# barnabas_noggin_V4.net
KiCad netlist of a schematic drawn in EAGLE
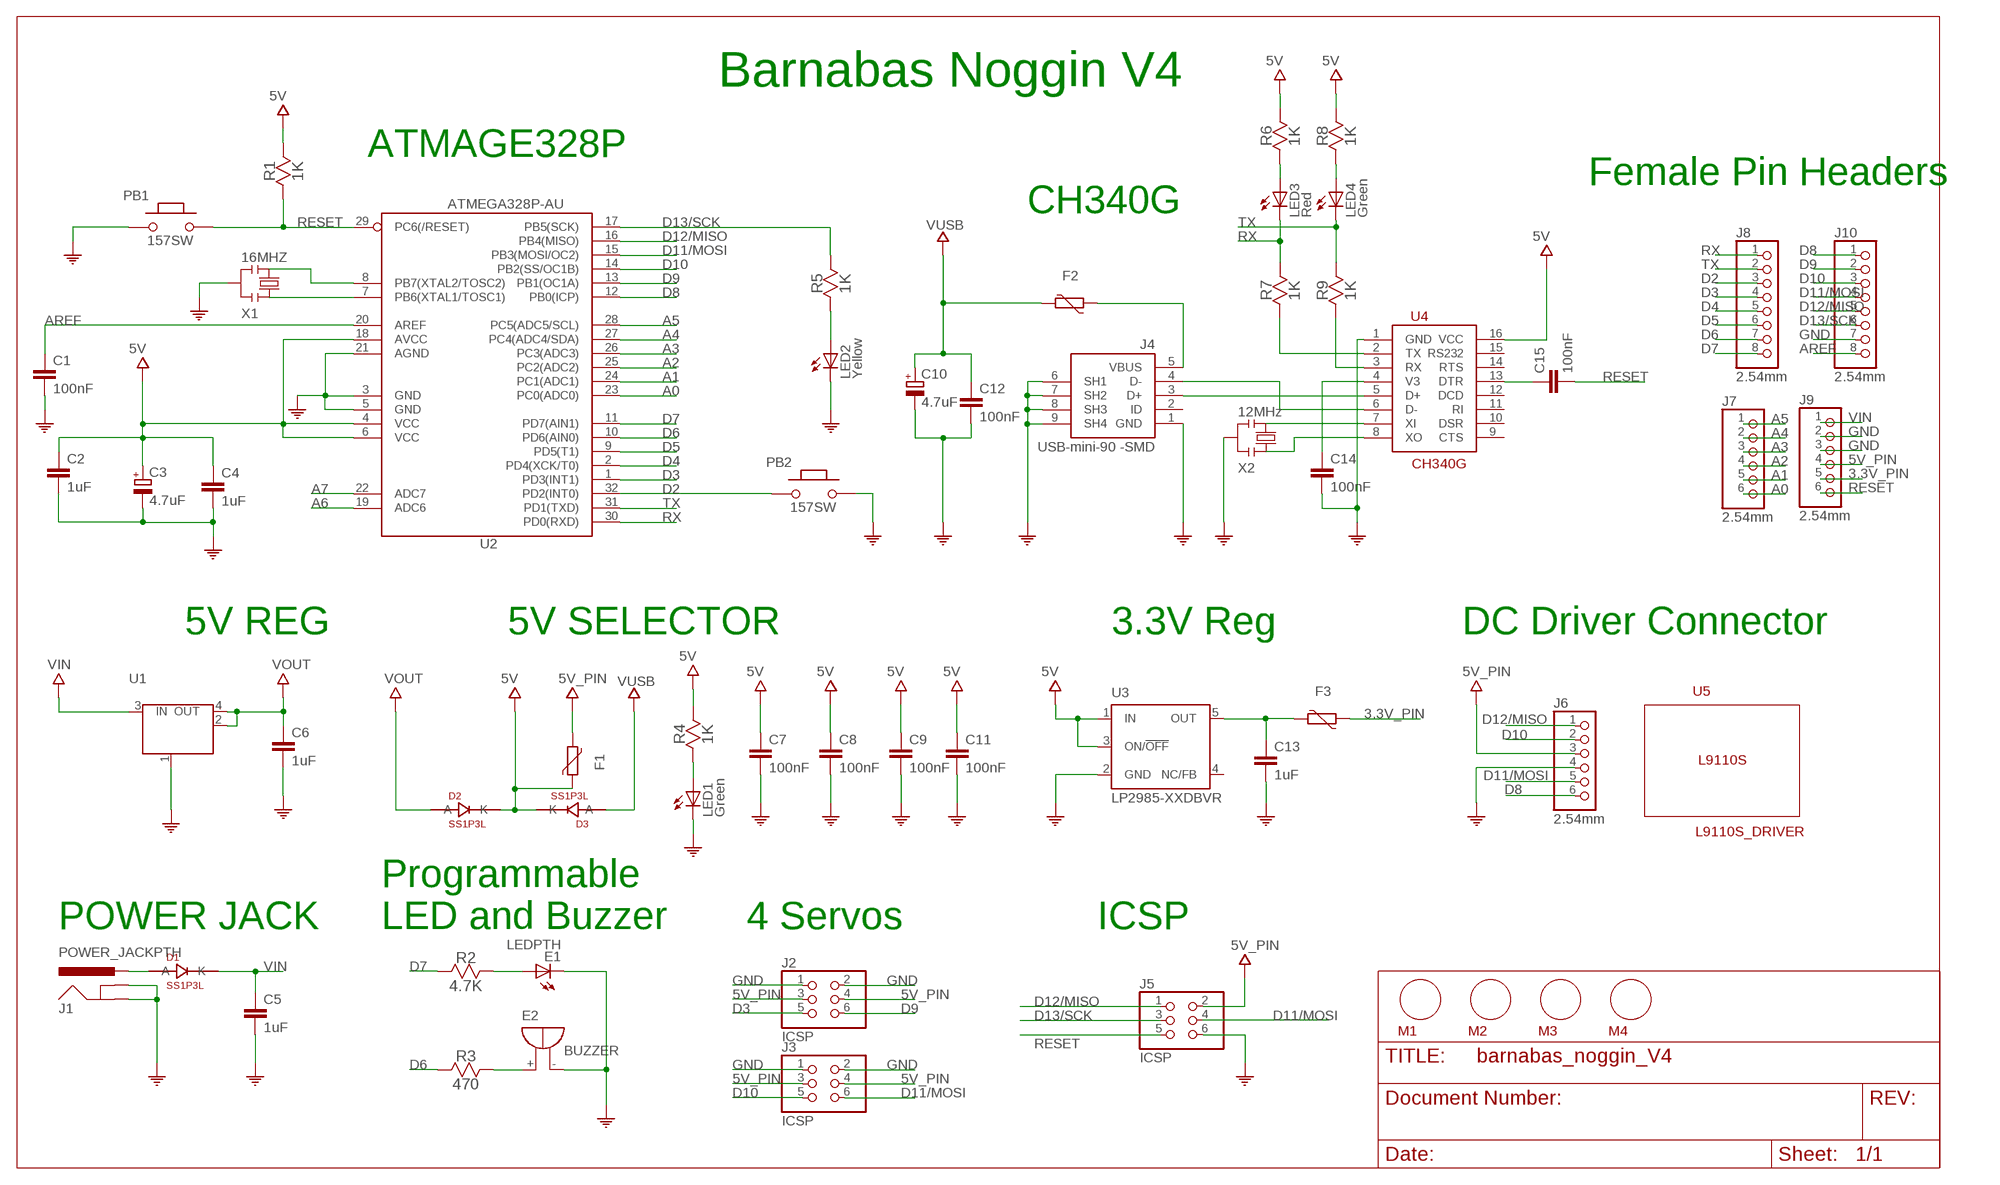
[diagram p0: schematic, sheet 1]

(export (version "E")
  (design (tool "Eeschema 10.0.6"))
  (components
    (comp (ref "C1")
      (value "100nF")
      (footprint "eagle-import:C0603-ROUND")
      (fields (field (name "PARTNO") "CC0603ZRY5V9BB104"))
      (libsource (lib "eagle-import") (part "CAPACITOR_100NF_0603"))
    )
    (comp (ref "C2")
      (value "1uF")
      (footprint "eagle-import:C0603-ROUND")
      (fields (field (name "PARTNO") "CC0603KRX5R8BB105"))
      (libsource (lib "eagle-import") (part "CAPACITOR_1UF_0603"))
    )
    (comp (ref "C3")
      (value "4.7uF")
      (footprint "eagle-import:TAN-A")
      (fields (field (name "PARTNO") "CL31A475KOHNNNE"))
      (libsource (lib "eagle-import") (part "CAPACITOR_4.7UF"))
    )
    (comp (ref "C4")
      (value "1uF")
      (footprint "eagle-import:C0603-ROUND")
      (fields (field (name "PARTNO") "CC0603KRX5R8BB105"))
      (libsource (lib "eagle-import") (part "CAPACITOR_1UF_0603"))
    )
    (comp (ref "C5")
      (value "1uF")
      (footprint "eagle-import:C0603-ROUND")
      (fields (field (name "PARTNO") "CC0603KRX5R8BB105"))
      (libsource (lib "eagle-import") (part "CAPACITOR_1UF_0603"))
    )
    (comp (ref "C6")
      (value "1uF")
      (footprint "eagle-import:C0603-ROUND")
      (fields (field (name "PARTNO") "CC0603KRX5R8BB105"))
      (libsource (lib "eagle-import") (part "CAPACITOR_1UF_0603"))
    )
    (comp (ref "C7")
      (value "100nF")
      (footprint "eagle-import:C0603-ROUND")
      (fields (field (name "PARTNO") "CC0603ZRY5V9BB104"))
      (libsource (lib "eagle-import") (part "CAPACITOR_100NF_0603"))
    )
    (comp (ref "C8")
      (value "100nF")
      (footprint "eagle-import:C0603-ROUND")
      (fields (field (name "PARTNO") "CC0603ZRY5V9BB104"))
      (libsource (lib "eagle-import") (part "CAPACITOR_100NF_0603"))
    )
    (comp (ref "C9")
      (value "100nF")
      (footprint "eagle-import:C0603-ROUND")
      (fields (field (name "PARTNO") "CC0603ZRY5V9BB104"))
      (libsource (lib "eagle-import") (part "CAPACITOR_100NF_0603"))
    )
    (comp (ref "C10")
      (value "4.7uF")
      (footprint "eagle-import:TAN-A")
      (fields (field (name "PARTNO") "CL31A475KOHNNNE"))
      (libsource (lib "eagle-import") (part "CAPACITOR_4.7UF"))
    )
    (comp (ref "C11")
      (value "100nF")
      (footprint "eagle-import:C0603-ROUND")
      (fields (field (name "PARTNO") "CC0603ZRY5V9BB104"))
      (libsource (lib "eagle-import") (part "CAPACITOR_100NF_0603"))
    )
    (comp (ref "C12")
      (value "100nF")
      (footprint "eagle-import:C0603-ROUND")
      (fields (field (name "PARTNO") "CC0603ZRY5V9BB104"))
      (libsource (lib "eagle-import") (part "CAPACITOR_100NF_0603"))
    )
    (comp (ref "C13")
      (value "1uF")
      (footprint "eagle-import:C0603-ROUND")
      (fields (field (name "PARTNO") "CC0603KRX5R8BB105"))
      (libsource (lib "eagle-import") (part "CAPACITOR_1UF_0603"))
    )
    (comp (ref "C14")
      (value "100nF")
      (footprint "eagle-import:C0603-ROUND")
      (fields (field (name "PARTNO") "CC0603ZRY5V9BB104"))
      (libsource (lib "eagle-import") (part "CAPACITOR_100NF_0603"))
    )
    (comp (ref "C15")
      (value "100nF")
      (footprint "eagle-import:C0603-ROUND")
      (fields (field (name "PARTNO") "CC0603ZRY5V9BB104"))
      (libsource (lib "eagle-import") (part "CAPACITOR_100NF_0603"))
    )
    (comp (ref "D1")
      (value "SS1P3L")
      (footprint "eagle-import:DIODI_DO220AAL")
      (fields (field (name "PARTNO") "SS1P3L-M3/84A"))
      (libsource (lib "eagle-import") (part "SCHOTTKY_DIODE"))
    )
    (comp (ref "D2")
      (value "SS1P3L")
      (footprint "eagle-import:DIODI_DO220AAL")
      (fields (field (name "PARTNO") "SS1P3L-M3/84A"))
      (libsource (lib "eagle-import") (part "SCHOTTKY_DIODE"))
    )
    (comp (ref "D3")
      (value "SS1P3L")
      (footprint "eagle-import:DIODI_DO220AAL")
      (fields (field (name "PARTNO") "SS1P3L-M3/84A"))
      (libsource (lib "eagle-import") (part "SCHOTTKY_DIODE"))
    )
    (comp (ref "E1")
      (value "LEDPTH")
      (footprint "eagle-import:LED5MM")
      (libsource (lib "eagle-import") (part "LEDPTH"))
    )
    (comp (ref "E2")
      (value "BUZZER")
      (footprint "eagle-import:BUZZER")
      (libsource (lib "eagle-import") (part "BUZZER"))
    )
    (comp (ref "F1")
      (value "FUSE_6V")
      (footprint "eagle-import:FUSE_0603")
      (fields (field (name "PARTNO") "MF-FSMF050X-2"))
      (libsource (lib "eagle-import") (part "FUSE_6V"))
    )
    (comp (ref "F2")
      (value "FUSE_6V")
      (footprint "eagle-import:FUSE_0603")
      (fields (field (name "PARTNO") "MF-FSMF050X-2"))
      (libsource (lib "eagle-import") (part "FUSE_6V"))
    )
    (comp (ref "F3")
      (value "FUSE_6V")
      (footprint "eagle-import:FUSE_0603")
      (fields (field (name "PARTNO") "MF-FSMF050X-2"))
      (libsource (lib "eagle-import") (part "FUSE_6V"))
    )
    (comp (ref "J1")
      (value "POWER_JACKPTH")
      (footprint "eagle-import:POWER_JACK_PTH")
      (fields (field (name "PARTNO") "EJ508A"))
      (libsource (lib "eagle-import") (part "POWER_JACKPTH"))
    )
    (comp (ref "J2")
      (value "ICSP")
      (footprint "eagle-import:CONNECTOR_2X3")
      (fields (field (name "PARTNO") "M20-9980346"))
      (libsource (lib "eagle-import") (part "CONNECTOR_2X3"))
    )
    (comp (ref "J3")
      (value "ICSP")
      (footprint "eagle-import:CONNECTOR_2X3")
      (fields (field (name "PARTNO") "M20-9980346"))
      (libsource (lib "eagle-import") (part "CONNECTOR_2X3"))
    )
    (comp (ref "J4")
      (value "USB-mini-90 -SMD")
      (footprint "eagle-import:CONNECTOR_USB_MINI-B")
      (fields (field (name "PARTNO") "UJ2-MBH-1-SMT-TR"))
      (libsource (lib "eagle-import") (part "CONNECTOR_USB_MINI-B"))
    )
    (comp (ref "J5")
      (value "ICSP")
      (footprint "eagle-import:CONNECTOR_2X3")
      (fields (field (name "PARTNO") "M20-9980346"))
      (libsource (lib "eagle-import") (part "CONNECTOR_2X3"))
    )
    (comp (ref "J6")
      (value "2.54mm")
      (footprint "eagle-import:1X06")
      (fields (field (name "PARTNO") "M20-7820646"))
      (libsource (lib "eagle-import") (part "PINHD-1X6"))
    )
    (comp (ref "J7")
      (value "2.54mm")
      (footprint "eagle-import:1X06")
      (fields (field (name "PARTNO") "M20-7820646"))
      (libsource (lib "eagle-import") (part "PINHD-1X6"))
    )
    (comp (ref "J8")
      (value "2.54mm")
      (footprint "eagle-import:1X08")
      (fields (field (name "PARTNO") "PPTC081LFBN-RC"))
      (libsource (lib "eagle-import") (part "PINHD-1X8"))
    )
    (comp (ref "J9")
      (value "2.54mm")
      (footprint "eagle-import:1X06")
      (fields (field (name "PARTNO") "M20-7820646"))
      (libsource (lib "eagle-import") (part "PINHD-1X6"))
    )
    (comp (ref "J10")
      (value "2.54mm")
      (footprint "eagle-import:1X08")
      (fields (field (name "PARTNO") "PPTC081LFBN-RC"))
      (libsource (lib "eagle-import") (part "PINHD-1X8"))
    )
    (comp (ref "LED1")
      (value "Green")
      (footprint "eagle-import:LED_0805")
      (fields (field (name "PARTNO") "LTST-C171GKT"))
      (libsource (lib "eagle-import") (part "LED_GREEN"))
    )
    (comp (ref "LED2")
      (value "Yellow")
      (footprint "eagle-import:LED_0805")
      (fields (field (name "PARTNO") "LTST-C171KSKT"))
      (libsource (lib "eagle-import") (part "LED_YELLOW"))
    )
    (comp (ref "LED3")
      (value "Red")
      (footprint "eagle-import:LED_0805")
      (fields (field (name "PARTNO") "LTST-C170KRKT"))
      (libsource (lib "eagle-import") (part "LED_RED"))
    )
    (comp (ref "LED4")
      (value "Green")
      (footprint "eagle-import:LED_0805")
      (fields (field (name "PARTNO") "LTST-C171GKT"))
      (libsource (lib "eagle-import") (part "LED_GREEN"))
    )
    (comp (ref "M1")
      (value "MOUNT_HOLE")
      (footprint "eagle-import:MOUNT_HOLE")
      (libsource (lib "eagle-import") (part "MOUNT_HOLE"))
    )
    (comp (ref "M2")
      (value "MOUNT_HOLE")
      (footprint "eagle-import:MOUNT_HOLE")
      (libsource (lib "eagle-import") (part "MOUNT_HOLE"))
    )
    (comp (ref "M3")
      (value "MOUNT_HOLE")
      (footprint "eagle-import:MOUNT_HOLE")
      (libsource (lib "eagle-import") (part "MOUNT_HOLE"))
    )
    (comp (ref "M4")
      (value "MOUNT_HOLE")
      (footprint "eagle-import:MOUNT_HOLE")
      (libsource (lib "eagle-import") (part "MOUNT_HOLE"))
    )
    (comp (ref "PB1")
      (value "157SW")
      (footprint "eagle-import:SWITCHES_SMD_157SW")
      (fields (field (name "PARTNO") "PTS820 J15M SMTR LFS"))
      (libsource (lib "eagle-import") (part "PUSHBUTTON"))
    )
    (comp (ref "PB2")
      (value "157SW")
      (footprint "eagle-import:SWITCHES_SMD_157SW")
      (fields (field (name "PARTNO") "PTS820 J15M SMTR LFS"))
      (libsource (lib "eagle-import") (part "PUSHBUTTON"))
    )
    (comp (ref "R1")
      (value "1K")
      (footprint "eagle-import:R0603")
      (fields (field (name "PARTNO") "RC0603FR-071KL "))
      (libsource (lib "eagle-import") (part "RESISTOR0603"))
    )
    (comp (ref "R2")
      (value "4.7K")
      (footprint "eagle-import:RESISTOR_PTH")
      (libsource (lib "eagle-import") (part "RESISTOR"))
    )
    (comp (ref "R3")
      (value "470")
      (footprint "eagle-import:RESISTOR_PTH")
      (libsource (lib "eagle-import") (part "RESISTOR"))
    )
    (comp (ref "R4")
      (value "1K")
      (footprint "eagle-import:R0603")
      (fields (field (name "PARTNO") "RC0603FR-071KL "))
      (libsource (lib "eagle-import") (part "RESISTOR0603"))
    )
    (comp (ref "R5")
      (value "1K")
      (footprint "eagle-import:R0603")
      (fields (field (name "PARTNO") "RC0603FR-071KL "))
      (libsource (lib "eagle-import") (part "RESISTOR0603"))
    )
    (comp (ref "R6")
      (value "1K")
      (footprint "eagle-import:R0603")
      (fields (field (name "PARTNO") "RC0603FR-071KL "))
      (libsource (lib "eagle-import") (part "RESISTOR0603"))
    )
    (comp (ref "R7")
      (value "1K")
      (footprint "eagle-import:R0603")
      (fields (field (name "PARTNO") "RC0603FR-071KL "))
      (libsource (lib "eagle-import") (part "RESISTOR0603"))
    )
    (comp (ref "R8")
      (value "1K")
      (footprint "eagle-import:R0603")
      (fields (field (name "PARTNO") "RC0603FR-071KL "))
      (libsource (lib "eagle-import") (part "RESISTOR0603"))
    )
    (comp (ref "R9")
      (value "1K")
      (footprint "eagle-import:R0603")
      (fields (field (name "PARTNO") "RC0603FR-071KL "))
      (libsource (lib "eagle-import") (part "RESISTOR0603"))
    )
    (comp (ref "U1")
      (value "LM1117IMPX-5.0")
      (footprint "eagle-import:LM1117_SOT223")
      (fields (field (name "PARTNO") "LM1117IMPX-5.0/NOPB"))
      (libsource (lib "eagle-import") (part "LM1117"))
    )
    (comp (ref "U2")
      (value "ATMEGA328P-AU")
      (footprint "eagle-import:TQFP32-08")
      (libsource (lib "eagle-import") (part "ATMEGA328P-32AU"))
    )
    (comp (ref "U3")
      (value "LP2985-XXDBVR")
      (footprint "eagle-import:SOT23-DBV")
      (fields (field (name "PARTNO") "LP2985-33DBVR"))
      (libsource (lib "eagle-import") (part "LP2985-XXDBVR"))
    )
    (comp (ref "U4")
      (value "CH340G")
      (footprint "eagle-import:SOIC16")
      (libsource (lib "eagle-import") (part "CH340G"))
    )
    (comp (ref "U5")
      (value "L9110S_DRIVER")
      (footprint "eagle-import:L9110S_DRIVER")
      (libsource (lib "eagle-import") (part "L9110S_DRIVER"))
    )
    (comp (ref "X1")
      (value "16MHZ")
      (footprint "eagle-import:CRYSTAL")
      (fields (field (name "PARTNO") "CSTNE16M0V530000R0"))
      (libsource (lib "eagle-import") (part "CRYSTAL_16MHZ"))
    )
    (comp (ref "X2")
      (value "12MHz")
      (footprint "eagle-import:CRYSTAL")
      (fields (field (name "PARTNO") "CSTNE12M0G550000R0"))
      (libsource (lib "eagle-import") (part "CRYSTAL_12MHZ"))
    )
  )
  (nets
    (net (code "1") (name "/3.3V_PIN") (class "Default")
      (node (ref "F3") (pin "1") (pinfunction "1_1") (pintype "passive"))
      (node (ref "J9") (pin "5") (pinfunction "5_5") (pintype "passive"))
    )
    (net (code "2") (name "/A0") (class "Default")
      (node (ref "J7") (pin "6") (pinfunction "6_6") (pintype "passive"))
      (node (ref "U2") (pin "23") (pinfunction "PC0(ADC0)_23") (pintype "bidirectional"))
    )
    (net (code "3") (name "/A1") (class "Default")
      (node (ref "J7") (pin "5") (pinfunction "5_5") (pintype "passive"))
      (node (ref "U2") (pin "24") (pinfunction "PC1(ADC1)_24") (pintype "bidirectional"))
    )
    (net (code "4") (name "/A2") (class "Default")
      (node (ref "J7") (pin "4") (pinfunction "4_4") (pintype "passive"))
      (node (ref "U2") (pin "25") (pinfunction "PC2(ADC2)_25") (pintype "bidirectional"))
    )
    (net (code "5") (name "/A3") (class "Default")
      (node (ref "J7") (pin "3") (pinfunction "3_3") (pintype "passive"))
      (node (ref "U2") (pin "26") (pinfunction "PC3(ADC3)_26") (pintype "bidirectional"))
    )
    (net (code "6") (name "/A4") (class "Default")
      (node (ref "J7") (pin "2") (pinfunction "2_2") (pintype "passive"))
      (node (ref "U2") (pin "27") (pinfunction "PC4(ADC4/SDA)_27") (pintype "bidirectional"))
    )
    (net (code "7") (name "/A5") (class "Default")
      (node (ref "J7") (pin "1") (pinfunction "1_1") (pintype "passive"))
      (node (ref "U2") (pin "28") (pinfunction "PC5(ADC5/SCL)_28") (pintype "bidirectional"))
    )
    (net (code "8") (name "/A6") (class "Default")
      (node (ref "U2") (pin "19") (pinfunction "ADC6_19") (pintype "bidirectional"))
    )
    (net (code "9") (name "/A7") (class "Default")
      (node (ref "U2") (pin "22") (pinfunction "ADC7_22") (pintype "bidirectional"))
    )
    (net (code "10") (name "/AREF") (class "Default")
      (node (ref "C1") (pin "1") (pinfunction "1_1") (pintype "passive"))
      (node (ref "J10") (pin "8") (pinfunction "8_8") (pintype "passive"))
      (node (ref "U2") (pin "20") (pinfunction "AREF_20") (pintype "bidirectional"))
    )
    (net (code "11") (name "/D2") (class "Default")
      (node (ref "J8") (pin "3") (pinfunction "3_3") (pintype "passive"))
      (node (ref "PB2") (pin "1") (pinfunction "1_1") (pintype "passive"))
      (node (ref "U2") (pin "32") (pinfunction "PD2(INT0)_32") (pintype "bidirectional"))
    )
    (net (code "12") (name "/D3") (class "Default")
      (node (ref "J2") (pin "5") (pinfunction "5_5") (pintype "passive"))
      (node (ref "J8") (pin "4") (pinfunction "4_4") (pintype "passive"))
      (node (ref "U2") (pin "1") (pinfunction "PD3(INT1)_1") (pintype "bidirectional"))
    )
    (net (code "13") (name "/D4") (class "Default")
      (node (ref "J8") (pin "5") (pinfunction "5_5") (pintype "passive"))
      (node (ref "U2") (pin "2") (pinfunction "PD4(XCK/T0)_2") (pintype "bidirectional"))
    )
    (net (code "14") (name "/D5") (class "Default")
      (node (ref "J8") (pin "6") (pinfunction "6_6") (pintype "passive"))
      (node (ref "U2") (pin "9") (pinfunction "PD5(T1)_9") (pintype "bidirectional"))
    )
    (net (code "15") (name "/D6") (class "Default")
      (node (ref "J8") (pin "7") (pinfunction "7_7") (pintype "passive"))
      (node (ref "R3") (pin "1") (pinfunction "1_1") (pintype "bidirectional"))
      (node (ref "U2") (pin "10") (pinfunction "PD6(AIN0)_10") (pintype "bidirectional"))
    )
    (net (code "16") (name "/D7") (class "Default")
      (node (ref "J8") (pin "8") (pinfunction "8_8") (pintype "passive"))
      (node (ref "R2") (pin "1") (pinfunction "1_1") (pintype "bidirectional"))
      (node (ref "U2") (pin "11") (pinfunction "PD7(AIN1)_11") (pintype "bidirectional"))
    )
    (net (code "17") (name "/D8") (class "Default")
      (node (ref "J10") (pin "1") (pinfunction "1_1") (pintype "passive"))
      (node (ref "J6") (pin "6") (pinfunction "6_6") (pintype "passive"))
      (node (ref "U2") (pin "12") (pinfunction "PB0(ICP)_12") (pintype "bidirectional"))
    )
    (net (code "18") (name "/D9") (class "Default")
      (node (ref "J10") (pin "2") (pinfunction "2_2") (pintype "passive"))
      (node (ref "J2") (pin "6") (pinfunction "6_6") (pintype "passive"))
      (node (ref "U2") (pin "13") (pinfunction "PB1(OC1A)_13") (pintype "bidirectional"))
    )
    (net (code "19") (name "/D10") (class "Default")
      (node (ref "J10") (pin "3") (pinfunction "3_3") (pintype "passive"))
      (node (ref "J3") (pin "5") (pinfunction "5_5") (pintype "passive"))
      (node (ref "J6") (pin "2") (pinfunction "2_2") (pintype "passive"))
      (node (ref "U2") (pin "14") (pinfunction "PB2(SS/OC1B)_14") (pintype "bidirectional"))
    )
    (net (code "20") (name "/D11{slash}MOSI") (class "Default")
      (node (ref "J10") (pin "4") (pinfunction "4_4") (pintype "passive"))
      (node (ref "J3") (pin "6") (pinfunction "6_6") (pintype "passive"))
      (node (ref "J5") (pin "4") (pinfunction "4_4") (pintype "passive"))
      (node (ref "J6") (pin "5") (pinfunction "5_5") (pintype "passive"))
      (node (ref "U2") (pin "15") (pinfunction "PB3(MOSI/OC2)_15") (pintype "bidirectional"))
    )
    (net (code "21") (name "/D12{slash}MISO") (class "Default")
      (node (ref "J10") (pin "5") (pinfunction "5_5") (pintype "passive"))
      (node (ref "J5") (pin "1") (pinfunction "1_1") (pintype "passive"))
      (node (ref "J6") (pin "1") (pinfunction "1_1") (pintype "passive"))
      (node (ref "U2") (pin "16") (pinfunction "PB4(MISO)_16") (pintype "bidirectional"))
    )
    (net (code "22") (name "/D13{slash}SCK") (class "Default")
      (node (ref "J10") (pin "6") (pinfunction "6_6") (pintype "passive"))
      (node (ref "J5") (pin "3") (pinfunction "3_3") (pintype "passive"))
      (node (ref "R5") (pin "2") (pinfunction "2_2") (pintype "bidirectional"))
      (node (ref "U2") (pin "17") (pinfunction "PB5(SCK)_17") (pintype "bidirectional"))
    )
    (net (code "23") (name "/RESET") (class "Default")
      (node (ref "C15") (pin "2") (pinfunction "2_2") (pintype "passive"))
      (node (ref "J5") (pin "5") (pinfunction "5_5") (pintype "passive"))
      (node (ref "J9") (pin "6") (pinfunction "6_6") (pintype "passive"))
      (node (ref "PB1") (pin "2") (pinfunction "2_2") (pintype "passive"))
      (node (ref "R1") (pin "1") (pinfunction "1_1") (pintype "bidirectional"))
      (node (ref "U2") (pin "29") (pinfunction "PC6(/RESET)_29") (pintype "bidirectional"))
    )
    (net (code "24") (name "/RX") (class "Default")
      (node (ref "J8") (pin "1") (pinfunction "1_1") (pintype "passive"))
      (node (ref "LED3") (pin "C") (pinfunction "C_C") (pintype "passive"))
      (node (ref "R7") (pin "2") (pinfunction "2_2") (pintype "bidirectional"))
      (node (ref "U2") (pin "30") (pinfunction "PD0(RXD)_30") (pintype "bidirectional"))
    )
    (net (code "25") (name "/TX") (class "Default")
      (node (ref "J8") (pin "2") (pinfunction "2_2") (pintype "passive"))
      (node (ref "LED4") (pin "C") (pinfunction "C_C") (pintype "passive"))
      (node (ref "R9") (pin "2") (pinfunction "2_2") (pintype "bidirectional"))
      (node (ref "U2") (pin "31") (pinfunction "PD1(TXD)_31") (pintype "bidirectional"))
    )
    (net (code "26") (name "5V") (class "Default")
      (node (ref "C11") (pin "1") (pinfunction "1_1") (pintype "passive"))
      (node (ref "C2") (pin "1") (pinfunction "1_1") (pintype "passive"))
      (node (ref "C3") (pin "1") (pinfunction "+_1") (pintype "passive"))
      (node (ref "C4") (pin "1") (pinfunction "1_1") (pintype "passive"))
      (node (ref "C7") (pin "1") (pinfunction "1_1") (pintype "passive"))
      (node (ref "C8") (pin "1") (pinfunction "1_1") (pintype "passive"))
      (node (ref "C9") (pin "1") (pinfunction "1_1") (pintype "passive"))
      (node (ref "D2") (pin "P$1") (pinfunction "K_P$1") (pintype "bidirectional"))
      (node (ref "D3") (pin "P$1") (pinfunction "K_P$1") (pintype "bidirectional"))
      (node (ref "F1") (pin "1") (pinfunction "1_1") (pintype "passive"))
      (node (ref "R1") (pin "2") (pinfunction "2_2") (pintype "bidirectional"))
      (node (ref "R4") (pin "2") (pinfunction "2_2") (pintype "bidirectional"))
      (node (ref "R6") (pin "2") (pinfunction "2_2") (pintype "bidirectional"))
      (node (ref "R8") (pin "2") (pinfunction "2_2") (pintype "bidirectional"))
      (node (ref "U2") (pin "18") (pinfunction "AVCC_18") (pintype "bidirectional"))
      (node (ref "U2") (pin "4") (pinfunction "VCC_4") (pintype "bidirectional"))
      (node (ref "U2") (pin "6") (pinfunction "VCC_6") (pintype "bidirectional"))
      (node (ref "U3") (pin "1") (pinfunction "IN_1") (pintype "input"))
      (node (ref "U3") (pin "3") (pinfunction "ON/~{OFF}_3") (pintype "input"))
      (node (ref "U4") (pin "16") (pinfunction "VCC_16") (pintype "bidirectional"))
    )
    (net (code "27") (name "5V_PIN") (class "Default")
      (node (ref "F1") (pin "2") (pinfunction "2_2") (pintype "passive"))
      (node (ref "J2") (pin "3") (pinfunction "3_3") (pintype "passive"))
      (node (ref "J2") (pin "4") (pinfunction "4_4") (pintype "passive"))
      (node (ref "J3") (pin "3") (pinfunction "3_3") (pintype "passive"))
      (node (ref "J3") (pin "4") (pinfunction "4_4") (pintype "passive"))
      (node (ref "J5") (pin "2") (pinfunction "2_2") (pintype "passive"))
      (node (ref "J6") (pin "3") (pinfunction "3_3") (pintype "passive"))
      (node (ref "J9") (pin "4") (pinfunction "4_4") (pintype "passive"))
    )
    (net (code "28") (name "GND") (class "Default")
      (node (ref "C1") (pin "2") (pinfunction "2_2") (pintype "passive"))
      (node (ref "C10") (pin "2") (pinfunction "-_2") (pintype "passive"))
      (node (ref "C11") (pin "2") (pinfunction "2_2") (pintype "passive"))
      (node (ref "C12") (pin "2") (pinfunction "2_2") (pintype "passive"))
      (node (ref "C13") (pin "2") (pinfunction "2_2") (pintype "passive"))
      (node (ref "C14") (pin "2") (pinfunction "2_2") (pintype "passive"))
      (node (ref "C2") (pin "2") (pinfunction "2_2") (pintype "passive"))
      (node (ref "C3") (pin "2") (pinfunction "-_2") (pintype "passive"))
      (node (ref "C4") (pin "2") (pinfunction "2_2") (pintype "passive"))
      (node (ref "C5") (pin "2") (pinfunction "2_2") (pintype "passive"))
      (node (ref "C6") (pin "2") (pinfunction "2_2") (pintype "passive"))
      (node (ref "C7") (pin "2") (pinfunction "2_2") (pintype "passive"))
      (node (ref "C8") (pin "2") (pinfunction "2_2") (pintype "passive"))
      (node (ref "C9") (pin "2") (pinfunction "2_2") (pintype "passive"))
      (node (ref "E1") (pin "K") (pinfunction "C_K") (pintype "passive"))
      (node (ref "E2") (pin "-") (pinfunction "-_-") (pintype "passive"))
      (node (ref "J1") (pin "GND") (pinfunction "GND_GND") (pintype "bidirectional"))
      (node (ref "J1") (pin "GNDBREAK") (pinfunction "GNDBREAK_GNDBREAK") (pintype "bidirectional"))
      (node (ref "J10") (pin "7") (pinfunction "7_7") (pintype "passive"))
      (node (ref "J2") (pin "1") (pinfunction "1_1") (pintype "passive"))
      (node (ref "J2") (pin "2") (pinfunction "2_2") (pintype "passive"))
      (node (ref "J3") (pin "1") (pinfunction "1_1") (pintype "passive"))
      (node (ref "J3") (pin "2") (pinfunction "2_2") (pintype "passive"))
      (node (ref "J4") (pin "1") (pinfunction "GND_1") (pintype "passive"))
      (node (ref "J4") (pin "6") (pinfunction "SH1_6") (pintype "passive"))
      (node (ref "J4") (pin "7") (pinfunction "SH2_7") (pintype "passive"))
      (node (ref "J4") (pin "8") (pinfunction "SH3_8") (pintype "passive"))
      (node (ref "J4") (pin "9") (pinfunction "SH4_9") (pintype "passive"))
      (node (ref "J5") (pin "6") (pinfunction "6_6") (pintype "passive"))
      (node (ref "J6") (pin "4") (pinfunction "4_4") (pintype "passive"))
      (node (ref "J9") (pin "2") (pinfunction "2_2") (pintype "passive"))
      (node (ref "J9") (pin "3") (pinfunction "3_3") (pintype "passive"))
      (node (ref "LED1") (pin "C") (pinfunction "C_C") (pintype "passive"))
      (node (ref "LED2") (pin "C") (pinfunction "C_C") (pintype "passive"))
      (node (ref "PB1") (pin "1") (pinfunction "1_1") (pintype "passive"))
      (node (ref "PB2") (pin "2") (pinfunction "2_2") (pintype "passive"))
      (node (ref "U1") (pin "1") (pinfunction "GND/ADJ_1") (pintype "input"))
      (node (ref "U2") (pin "21") (pinfunction "AGND_21") (pintype "bidirectional"))
      (node (ref "U2") (pin "3") (pinfunction "GND_3") (pintype "bidirectional"))
      (node (ref "U2") (pin "5") (pinfunction "GND_5") (pintype "bidirectional"))
      (node (ref "U3") (pin "2") (pinfunction "GND_2") (pintype "power_in"))
      (node (ref "U4") (pin "1") (pinfunction "GND_1") (pintype "bidirectional"))
      (node (ref "X1") (pin "2") (pinfunction "2_2") (pintype "passive"))
      (node (ref "X2") (pin "2") (pinfunction "2_2") (pintype "passive"))
    )
    (net (code "29") (name "Net-(D1-A)") (class "Default")
      (node (ref "D1") (pin "P$2") (pinfunction "A_P$2") (pintype "bidirectional"))
      (node (ref "J1") (pin "PWR") (pinfunction "PWR_PWR") (pintype "bidirectional"))
    )
    (net (code "30") (name "Net-(E1-PadA)") (class "Default")
      (node (ref "E1") (pin "A") (pinfunction "A_A") (pintype "passive"))
      (node (ref "R2") (pin "2") (pinfunction "2_2") (pintype "bidirectional"))
    )
    (net (code "31") (name "Net-(E2-Pad+)") (class "Default")
      (node (ref "E2") (pin "+") (pinfunction "+_+") (pintype "passive"))
      (node (ref "R3") (pin "2") (pinfunction "2_2") (pintype "bidirectional"))
    )
    (net (code "32") (name "Net-(J4-D+)") (class "Default")
      (node (ref "J4") (pin "3") (pinfunction "D+_3") (pintype "bidirectional"))
      (node (ref "U4") (pin "5") (pinfunction "D+_5") (pintype "bidirectional"))
    )
    (net (code "33") (name "Net-(J4-D-)") (class "Default")
      (node (ref "J4") (pin "4") (pinfunction "D-_4") (pintype "bidirectional"))
      (node (ref "U4") (pin "6") (pinfunction "D-_6") (pintype "bidirectional"))
    )
    (net (code "34") (name "Net-(J4-VBUS)") (class "Default")
      (node (ref "F2") (pin "1") (pinfunction "1_1") (pintype "passive"))
      (node (ref "J4") (pin "5") (pinfunction "VBUS_5") (pintype "power_in"))
    )
    (net (code "35") (name "Net-(LED1-PadA)") (class "Default")
      (node (ref "LED1") (pin "A") (pinfunction "A_A") (pintype "passive"))
      (node (ref "R4") (pin "1") (pinfunction "1_1") (pintype "bidirectional"))
    )
    (net (code "36") (name "Net-(LED2-PadA)") (class "Default")
      (node (ref "LED2") (pin "A") (pinfunction "A_A") (pintype "passive"))
      (node (ref "R5") (pin "1") (pinfunction "1_1") (pintype "bidirectional"))
    )
    (net (code "37") (name "Net-(LED3-PadA)") (class "Default")
      (node (ref "LED3") (pin "A") (pinfunction "A_A") (pintype "passive"))
      (node (ref "R6") (pin "1") (pinfunction "1_1") (pintype "bidirectional"))
    )
    (net (code "38") (name "Net-(LED4-PadA)") (class "Default")
      (node (ref "LED4") (pin "A") (pinfunction "A_A") (pintype "passive"))
      (node (ref "R8") (pin "1") (pinfunction "1_1") (pintype "bidirectional"))
    )
    (net (code "39") (name "Net-(U2-PB6(XTAL1{slash}TOSC1))") (class "Default")
      (node (ref "U2") (pin "7") (pinfunction "PB6(XTAL1/TOSC1)_7") (pintype "bidirectional"))
      (node (ref "X1") (pin "1") (pinfunction "1_1") (pintype "passive"))
    )
    (net (code "40") (name "Net-(U2-PB7(XTAL2{slash}TOSC2))") (class "Default")
      (node (ref "U2") (pin "8") (pinfunction "PB7(XTAL2/TOSC2)_8") (pintype "bidirectional"))
      (node (ref "X1") (pin "3") (pinfunction "3_3") (pintype "passive"))
    )
    (net (code "41") (name "Net-(U3-OUT)") (class "Default")
      (node (ref "C13") (pin "1") (pinfunction "1_1") (pintype "passive"))
      (node (ref "F3") (pin "2") (pinfunction "2_2") (pintype "passive"))
      (node (ref "U3") (pin "5") (pinfunction "OUT_5") (pintype "passive"))
    )
    (net (code "42") (name "Net-(U4-DTR)") (class "Default")
      (node (ref "C15") (pin "1") (pinfunction "1_1") (pintype "passive"))
      (node (ref "U4") (pin "13") (pinfunction "DTR_13") (pintype "bidirectional"))
    )
    (net (code "43") (name "Net-(U4-RX)") (class "Default")
      (node (ref "R9") (pin "1") (pinfunction "1_1") (pintype "bidirectional"))
      (node (ref "U4") (pin "3") (pinfunction "RX_3") (pintype "bidirectional"))
    )
    (net (code "44") (name "Net-(U4-TX)") (class "Default")
      (node (ref "R7") (pin "1") (pinfunction "1_1") (pintype "bidirectional"))
      (node (ref "U4") (pin "2") (pinfunction "TX_2") (pintype "bidirectional"))
    )
    (net (code "45") (name "Net-(U4-V3)") (class "Default")
      (node (ref "C14") (pin "1") (pinfunction "1_1") (pintype "passive"))
      (node (ref "U4") (pin "4") (pinfunction "V3_4") (pintype "bidirectional"))
    )
    (net (code "46") (name "Net-(U4-XI)") (class "Default")
      (node (ref "U4") (pin "7") (pinfunction "XI_7") (pintype "bidirectional"))
      (node (ref "X2") (pin "3") (pinfunction "3_3") (pintype "passive"))
    )
    (net (code "47") (name "Net-(U4-XO)") (class "Default")
      (node (ref "U4") (pin "8") (pinfunction "XO_8") (pintype "bidirectional"))
      (node (ref "X2") (pin "1") (pinfunction "1_1") (pintype "passive"))
    )
    (net (code "48") (name "VIN") (class "Default")
      (node (ref "C5") (pin "1") (pinfunction "1_1") (pintype "passive"))
      (node (ref "D1") (pin "P$1") (pinfunction "K_P$1") (pintype "bidirectional"))
      (node (ref "J9") (pin "1") (pinfunction "1_1") (pintype "passive"))
      (node (ref "U1") (pin "3") (pinfunction "IN_3") (pintype "input"))
    )
    (net (code "49") (name "VOUT") (class "Default")
      (node (ref "C6") (pin "1") (pinfunction "1_1") (pintype "passive"))
      (node (ref "D2") (pin "P$2") (pinfunction "A_P$2") (pintype "bidirectional"))
      (node (ref "U1") (pin "2") (pinfunction "OUT_2") (pintype "passive"))
      (node (ref "U1") (pin "4") (pinfunction "OUT_4") (pintype "passive"))
    )
    (net (code "50") (name "VUSB") (class "Default")
      (node (ref "C10") (pin "1") (pinfunction "+_1") (pintype "passive"))
      (node (ref "C12") (pin "1") (pinfunction "1_1") (pintype "passive"))
      (node (ref "D3") (pin "P$2") (pinfunction "A_P$2") (pintype "bidirectional"))
      (node (ref "F2") (pin "2") (pinfunction "2_2") (pintype "passive"))
    )
    (net (code "51") (name "unconnected-(J4-ID-Pad2)") (class "Default")
      (node (ref "J4") (pin "2") (pinfunction "ID_2") (pintype "bidirectional"))
    )
    (net (code "52") (name "unconnected-(U3-NC{slash}FB-Pad4)") (class "Default")
      (node (ref "U3") (pin "4") (pinfunction "NC/FB_4") (pintype "passive"))
    )
    (net (code "53") (name "unconnected-(U4-CTS-Pad9)") (class "Default")
      (node (ref "U4") (pin "9") (pinfunction "CTS_9") (pintype "bidirectional"))
    )
    (net (code "54") (name "unconnected-(U4-DCD-Pad12)") (class "Default")
      (node (ref "U4") (pin "12") (pinfunction "DCD_12") (pintype "bidirectional"))
    )
    (net (code "55") (name "unconnected-(U4-DSR-Pad10)") (class "Default")
      (node (ref "U4") (pin "10") (pinfunction "DSR_10") (pintype "bidirectional"))
    )
    (net (code "56") (name "unconnected-(U4-RI-Pad11)") (class "Default")
      (node (ref "U4") (pin "11") (pinfunction "RI_11") (pintype "bidirectional"))
    )
    (net (code "57") (name "unconnected-(U4-RS232-Pad15)") (class "Default")
      (node (ref "U4") (pin "15") (pinfunction "RS232_15") (pintype "bidirectional"))
    )
    (net (code "58") (name "unconnected-(U4-RTS-Pad14)") (class "Default")
      (node (ref "U4") (pin "14") (pinfunction "RTS_14") (pintype "bidirectional"))
    )
  )
)
